# st_ekg_v1.net
KiCad netlist of a schematic drawn in EAGLE
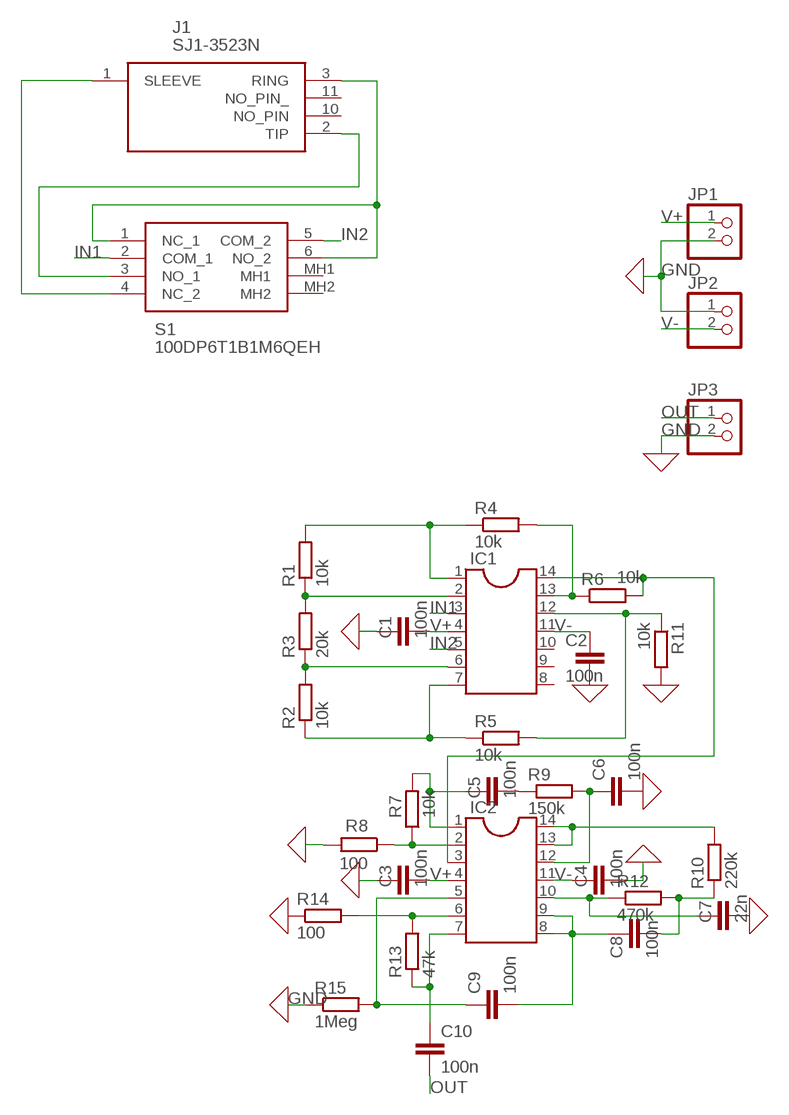
[diagram p0: schematic, sheet 1]

(export (version "E")
  (design (tool "Eeschema 10.0.6"))
  (components
    (comp (ref "C1")
      (value "100n")
      (footprint "eagle-import:C0805")
      (libsource (lib "eagle-import") (part "C-EUC0805"))
    )
    (comp (ref "C2")
      (value "100n")
      (footprint "eagle-import:C0805")
      (libsource (lib "eagle-import") (part "C-EUC0805"))
    )
    (comp (ref "C3")
      (value "100n")
      (footprint "eagle-import:C0805")
      (libsource (lib "eagle-import") (part "C-EUC0805"))
    )
    (comp (ref "C4")
      (value "100n")
      (footprint "eagle-import:C0805")
      (libsource (lib "eagle-import") (part "C-EUC0805"))
    )
    (comp (ref "C5")
      (value "100n")
      (footprint "eagle-import:C0805")
      (libsource (lib "eagle-import") (part "C-EUC0805"))
    )
    (comp (ref "C6")
      (value "100n")
      (footprint "eagle-import:C0805")
      (libsource (lib "eagle-import") (part "C-EUC0805"))
    )
    (comp (ref "C7")
      (value "22n")
      (footprint "eagle-import:C0805")
      (libsource (lib "eagle-import") (part "C-EUC0805"))
    )
    (comp (ref "C8")
      (value "100n")
      (footprint "eagle-import:C0805")
      (libsource (lib "eagle-import") (part "C-EUC0805"))
    )
    (comp (ref "C9")
      (value "100n")
      (footprint "eagle-import:C0805")
      (libsource (lib "eagle-import") (part "C-EUC0805"))
    )
    (comp (ref "C10")
      (value "100n")
      (footprint "eagle-import:C0805")
      (libsource (lib "eagle-import") (part "C-EUC0805"))
    )
    (comp (ref "IC1")
      (value "DIL14S")
      (footprint "eagle-import:SOCKET-14")
      (libsource (lib "eagle-import") (part "DIL14S"))
    )
    (comp (ref "IC2")
      (value "DIL14S")
      (footprint "eagle-import:SOCKET-14")
      (libsource (lib "eagle-import") (part "DIL14S"))
    )
    (comp (ref "J1")
      (value "SJ1-3523N")
      (footprint "eagle-import:SJ13523N")
      (fields (field (name "MOUSER_PART_NUMBER") "490-SJ1-3523N"))
      (libsource (lib "eagle-import") (part "SJ1-3523N"))
    )
    (comp (ref "JP1")
      (value "PINHD-1X2")
      (footprint "eagle-import:1X02")
      (libsource (lib "eagle-import") (part "PINHD-1X2"))
    )
    (comp (ref "JP2")
      (value "PINHD-1X2")
      (footprint "eagle-import:1X02")
      (libsource (lib "eagle-import") (part "PINHD-1X2"))
    )
    (comp (ref "JP3")
      (value "PINHD-1X2")
      (footprint "eagle-import:1X02")
      (libsource (lib "eagle-import") (part "PINHD-1X2"))
    )
    (comp (ref "R1")
      (value "10k")
      (footprint "eagle-import:M0805")
      (libsource (lib "eagle-import") (part "R-EU_M0805"))
    )
    (comp (ref "R2")
      (value "10k")
      (footprint "eagle-import:M0805")
      (libsource (lib "eagle-import") (part "R-EU_M0805"))
    )
    (comp (ref "R3")
      (value "20k")
      (footprint "eagle-import:M0805")
      (libsource (lib "eagle-import") (part "R-EU_M0805"))
    )
    (comp (ref "R4")
      (value "10k")
      (footprint "eagle-import:M0805")
      (libsource (lib "eagle-import") (part "R-EU_M0805"))
    )
    (comp (ref "R5")
      (value "10k")
      (footprint "eagle-import:M0805")
      (libsource (lib "eagle-import") (part "R-EU_M0805"))
    )
    (comp (ref "R6")
      (value "10k")
      (footprint "eagle-import:M0805")
      (libsource (lib "eagle-import") (part "R-EU_M0805"))
    )
    (comp (ref "R7")
      (value "10k")
      (footprint "eagle-import:M0805")
      (libsource (lib "eagle-import") (part "R-EU_M0805"))
    )
    (comp (ref "R8")
      (value "100")
      (footprint "eagle-import:M0805")
      (libsource (lib "eagle-import") (part "R-EU_M0805"))
    )
    (comp (ref "R9")
      (value "150k")
      (footprint "eagle-import:M0805")
      (libsource (lib "eagle-import") (part "R-EU_M0805"))
    )
    (comp (ref "R10")
      (value "220k")
      (footprint "eagle-import:M0805")
      (libsource (lib "eagle-import") (part "R-EU_M0805"))
    )
    (comp (ref "R11")
      (value "10k")
      (footprint "eagle-import:M0805")
      (libsource (lib "eagle-import") (part "R-EU_M0805"))
    )
    (comp (ref "R12")
      (value "470k")
      (footprint "eagle-import:M0805")
      (libsource (lib "eagle-import") (part "R-EU_M0805"))
    )
    (comp (ref "R13")
      (value "47k")
      (footprint "eagle-import:M0805")
      (libsource (lib "eagle-import") (part "R-EU_M0805"))
    )
    (comp (ref "R14")
      (value "100")
      (footprint "eagle-import:M0805")
      (libsource (lib "eagle-import") (part "R-EU_M0805"))
    )
    (comp (ref "R15")
      (value "1Meg")
      (footprint "eagle-import:M0805")
      (libsource (lib "eagle-import") (part "R-EU_M0805"))
    )
    (comp (ref "S1")
      (value "100DP6T1B1M6QEH")
      (footprint "eagle-import:100DP6T1B1M6QEH")
      (fields (field (name "MOUSER_PART_NUMBER") "612-100DP6T1B1M6QEH"))
      (libsource (lib "eagle-import") (part "100DP6T1B1M6QEH"))
    )
  )
  (nets
    (net (code "1") (name "/IN1") (class "Default")
      (node (ref "IC1") (pin "3") (pinfunction "3_3") (pintype "passive"))
      (node (ref "S1") (pin "2") (pinfunction "COM_1_2") (pintype "bidirectional"))
    )
    (net (code "2") (name "/IN2") (class "Default")
      (node (ref "IC1") (pin "5") (pinfunction "5_5") (pintype "passive"))
      (node (ref "S1") (pin "5") (pinfunction "COM_2_5") (pintype "bidirectional"))
    )
    (net (code "3") (name "/OUT") (class "Default")
      (node (ref "C10") (pin "2") (pinfunction "2_2") (pintype "passive"))
      (node (ref "JP3") (pin "1") (pinfunction "1_1") (pintype "passive"))
    )
    (net (code "4") (name "/V+") (class "Default")
      (node (ref "C1") (pin "2") (pinfunction "2_2") (pintype "passive"))
      (node (ref "C3") (pin "2") (pinfunction "2_2") (pintype "passive"))
      (node (ref "IC1") (pin "4") (pinfunction "4_4") (pintype "passive"))
      (node (ref "IC2") (pin "4") (pinfunction "4_4") (pintype "passive"))
      (node (ref "JP1") (pin "1") (pinfunction "1_1") (pintype "passive"))
    )
    (net (code "5") (name "/V-") (class "Default")
      (node (ref "C2") (pin "1") (pinfunction "1_1") (pintype "passive"))
      (node (ref "C4") (pin "1") (pinfunction "1_1") (pintype "passive"))
      (node (ref "IC1") (pin "11") (pinfunction "11_11") (pintype "passive"))
      (node (ref "IC2") (pin "11") (pinfunction "11_11") (pintype "passive"))
      (node (ref "JP2") (pin "2") (pinfunction "2_2") (pintype "passive"))
    )
    (net (code "6") (name "GND") (class "Default")
      (node (ref "C1") (pin "1") (pinfunction "1_1") (pintype "passive"))
      (node (ref "C2") (pin "2") (pinfunction "2_2") (pintype "passive"))
      (node (ref "C3") (pin "1") (pinfunction "1_1") (pintype "passive"))
      (node (ref "C4") (pin "2") (pinfunction "2_2") (pintype "passive"))
      (node (ref "C6") (pin "2") (pinfunction "2_2") (pintype "passive"))
      (node (ref "C7") (pin "2") (pinfunction "2_2") (pintype "passive"))
      (node (ref "JP1") (pin "2") (pinfunction "2_2") (pintype "passive"))
      (node (ref "JP2") (pin "1") (pinfunction "1_1") (pintype "passive"))
      (node (ref "JP3") (pin "2") (pinfunction "2_2") (pintype "passive"))
      (node (ref "R11") (pin "2") (pinfunction "2_2") (pintype "passive"))
      (node (ref "R14") (pin "1") (pinfunction "1_1") (pintype "passive"))
      (node (ref "R15") (pin "1") (pinfunction "1_1") (pintype "passive"))
      (node (ref "R8") (pin "2") (pinfunction "2_2") (pintype "passive"))
    )
    (net (code "7") (name "Net-(C5-Pad1)") (class "Default")
      (node (ref "C5") (pin "1") (pinfunction "1_1") (pintype "passive"))
      (node (ref "IC2") (pin "1") (pinfunction "1_1") (pintype "passive"))
      (node (ref "R7") (pin "2") (pinfunction "2_2") (pintype "passive"))
    )
    (net (code "8") (name "Net-(C5-Pad2)") (class "Default")
      (node (ref "C5") (pin "2") (pinfunction "2_2") (pintype "passive"))
      (node (ref "R9") (pin "1") (pinfunction "1_1") (pintype "passive"))
    )
    (net (code "9") (name "Net-(C6-Pad1)") (class "Default")
      (node (ref "C6") (pin "1") (pinfunction "1_1") (pintype "passive"))
      (node (ref "IC2") (pin "12") (pinfunction "12_12") (pintype "passive"))
      (node (ref "R9") (pin "2") (pinfunction "2_2") (pintype "passive"))
    )
    (net (code "10") (name "Net-(C7-Pad1)") (class "Default")
      (node (ref "C7") (pin "1") (pinfunction "1_1") (pintype "passive"))
      (node (ref "IC2") (pin "10") (pinfunction "10_10") (pintype "passive"))
      (node (ref "R12") (pin "1") (pinfunction "1_1") (pintype "passive"))
    )
    (net (code "11") (name "Net-(C8-Pad1)") (class "Default")
      (node (ref "C8") (pin "1") (pinfunction "1_1") (pintype "passive"))
      (node (ref "C9") (pin "2") (pinfunction "2_2") (pintype "passive"))
      (node (ref "IC2") (pin "8") (pinfunction "8_8") (pintype "passive"))
      (node (ref "IC2") (pin "9") (pinfunction "9_9") (pintype "passive"))
    )
    (net (code "12") (name "Net-(C8-Pad2)") (class "Default")
      (node (ref "C8") (pin "2") (pinfunction "2_2") (pintype "passive"))
      (node (ref "R10") (pin "1") (pinfunction "1_1") (pintype "passive"))
      (node (ref "R12") (pin "2") (pinfunction "2_2") (pintype "passive"))
    )
    (net (code "13") (name "Net-(C9-Pad1)") (class "Default")
      (node (ref "C9") (pin "1") (pinfunction "1_1") (pintype "passive"))
      (node (ref "IC2") (pin "5") (pinfunction "5_5") (pintype "passive"))
      (node (ref "R15") (pin "2") (pinfunction "2_2") (pintype "passive"))
    )
    (net (code "14") (name "Net-(C10-Pad1)") (class "Default")
      (node (ref "C10") (pin "1") (pinfunction "1_1") (pintype "passive"))
      (node (ref "IC2") (pin "7") (pinfunction "7_7") (pintype "passive"))
      (node (ref "R13") (pin "1") (pinfunction "1_1") (pintype "passive"))
    )
    (net (code "15") (name "Net-(IC1-Pad1)") (class "Default")
      (node (ref "IC1") (pin "1") (pinfunction "1_1") (pintype "passive"))
      (node (ref "R1") (pin "2") (pinfunction "2_2") (pintype "passive"))
      (node (ref "R4") (pin "1") (pinfunction "1_1") (pintype "passive"))
    )
    (net (code "16") (name "Net-(IC1-Pad2)") (class "Default")
      (node (ref "IC1") (pin "2") (pinfunction "2_2") (pintype "passive"))
      (node (ref "R1") (pin "1") (pinfunction "1_1") (pintype "passive"))
      (node (ref "R3") (pin "2") (pinfunction "2_2") (pintype "passive"))
    )
    (net (code "17") (name "Net-(IC1-Pad6)") (class "Default")
      (node (ref "IC1") (pin "6") (pinfunction "6_6") (pintype "passive"))
      (node (ref "R2") (pin "2") (pinfunction "2_2") (pintype "passive"))
      (node (ref "R3") (pin "1") (pinfunction "1_1") (pintype "passive"))
    )
    (net (code "18") (name "Net-(IC1-Pad7)") (class "Default")
      (node (ref "IC1") (pin "7") (pinfunction "7_7") (pintype "passive"))
      (node (ref "R2") (pin "1") (pinfunction "1_1") (pintype "passive"))
      (node (ref "R5") (pin "1") (pinfunction "1_1") (pintype "passive"))
    )
    (net (code "19") (name "Net-(IC1-Pad12)") (class "Default")
      (node (ref "IC1") (pin "12") (pinfunction "12_12") (pintype "passive"))
      (node (ref "R11") (pin "1") (pinfunction "1_1") (pintype "passive"))
      (node (ref "R5") (pin "2") (pinfunction "2_2") (pintype "passive"))
    )
    (net (code "20") (name "Net-(IC1-Pad13)") (class "Default")
      (node (ref "IC1") (pin "13") (pinfunction "13_13") (pintype "passive"))
      (node (ref "R4") (pin "2") (pinfunction "2_2") (pintype "passive"))
      (node (ref "R6") (pin "1") (pinfunction "1_1") (pintype "passive"))
    )
    (net (code "21") (name "Net-(IC1-Pad14)") (class "Default")
      (node (ref "IC1") (pin "14") (pinfunction "14_14") (pintype "passive"))
      (node (ref "IC2") (pin "3") (pinfunction "3_3") (pintype "passive"))
      (node (ref "R6") (pin "2") (pinfunction "2_2") (pintype "passive"))
    )
    (net (code "22") (name "Net-(IC2-Pad2)") (class "Default")
      (node (ref "IC2") (pin "2") (pinfunction "2_2") (pintype "passive"))
      (node (ref "R7") (pin "1") (pinfunction "1_1") (pintype "passive"))
      (node (ref "R8") (pin "1") (pinfunction "1_1") (pintype "passive"))
    )
    (net (code "23") (name "Net-(IC2-Pad6)") (class "Default")
      (node (ref "IC2") (pin "6") (pinfunction "6_6") (pintype "passive"))
      (node (ref "R13") (pin "2") (pinfunction "2_2") (pintype "passive"))
      (node (ref "R14") (pin "2") (pinfunction "2_2") (pintype "passive"))
    )
    (net (code "24") (name "Net-(IC2-Pad13)") (class "Default")
      (node (ref "IC2") (pin "13") (pinfunction "13_13") (pintype "passive"))
      (node (ref "IC2") (pin "14") (pinfunction "14_14") (pintype "passive"))
      (node (ref "R10") (pin "2") (pinfunction "2_2") (pintype "passive"))
    )
    (net (code "25") (name "Net-(J1-RING)") (class "Default")
      (node (ref "J1") (pin "3") (pinfunction "RING_3") (pintype "bidirectional"))
      (node (ref "S1") (pin "1") (pinfunction "NC_1_1") (pintype "bidirectional"))
      (node (ref "S1") (pin "6") (pinfunction "NO_2_6") (pintype "bidirectional"))
    )
    (net (code "26") (name "Net-(J1-SLEEVE)") (class "Default")
      (node (ref "J1") (pin "1") (pinfunction "SLEEVE_1") (pintype "bidirectional"))
      (node (ref "S1") (pin "4") (pinfunction "NC_2_4") (pintype "bidirectional"))
    )
    (net (code "27") (name "Net-(J1-TIP)") (class "Default")
      (node (ref "J1") (pin "2") (pinfunction "TIP_2") (pintype "bidirectional"))
      (node (ref "S1") (pin "3") (pinfunction "NO_1_3") (pintype "bidirectional"))
    )
    (net (code "28") (name "unconnected-(IC1-Pad8)") (class "Default")
      (node (ref "IC1") (pin "8") (pinfunction "8_8") (pintype "passive"))
    )
    (net (code "29") (name "unconnected-(IC1-Pad9)") (class "Default")
      (node (ref "IC1") (pin "9") (pinfunction "9_9") (pintype "passive"))
    )
    (net (code "30") (name "unconnected-(IC1-Pad10)") (class "Default")
      (node (ref "IC1") (pin "10") (pinfunction "10_10") (pintype "passive"))
    )
    (net (code "31") (name "unconnected-(J1-NO_PIN-Pad10)") (class "Default")
      (node (ref "J1") (pin "10") (pinfunction "NO_PIN_10") (pintype "bidirectional"))
    )
    (net (code "32") (name "unconnected-(J1-NO_PIN_-Pad11)") (class "Default")
      (node (ref "J1") (pin "11") (pinfunction "NO_PIN__11") (pintype "bidirectional"))
    )
    (net (code "33") (name "unconnected-(S1-PadMH1)") (class "Default")
      (node (ref "S1") (pin "MH1") (pinfunction "MH1_MH1") (pintype "bidirectional"))
    )
    (net (code "34") (name "unconnected-(S1-PadMH2)") (class "Default")
      (node (ref "S1") (pin "MH2") (pinfunction "MH2_MH2") (pintype "bidirectional"))
    )
  )
)
